# Lamp_Logic_Board_20_BRAIN_3_legs.net
KiCad netlist of a schematic drawn in EAGLE
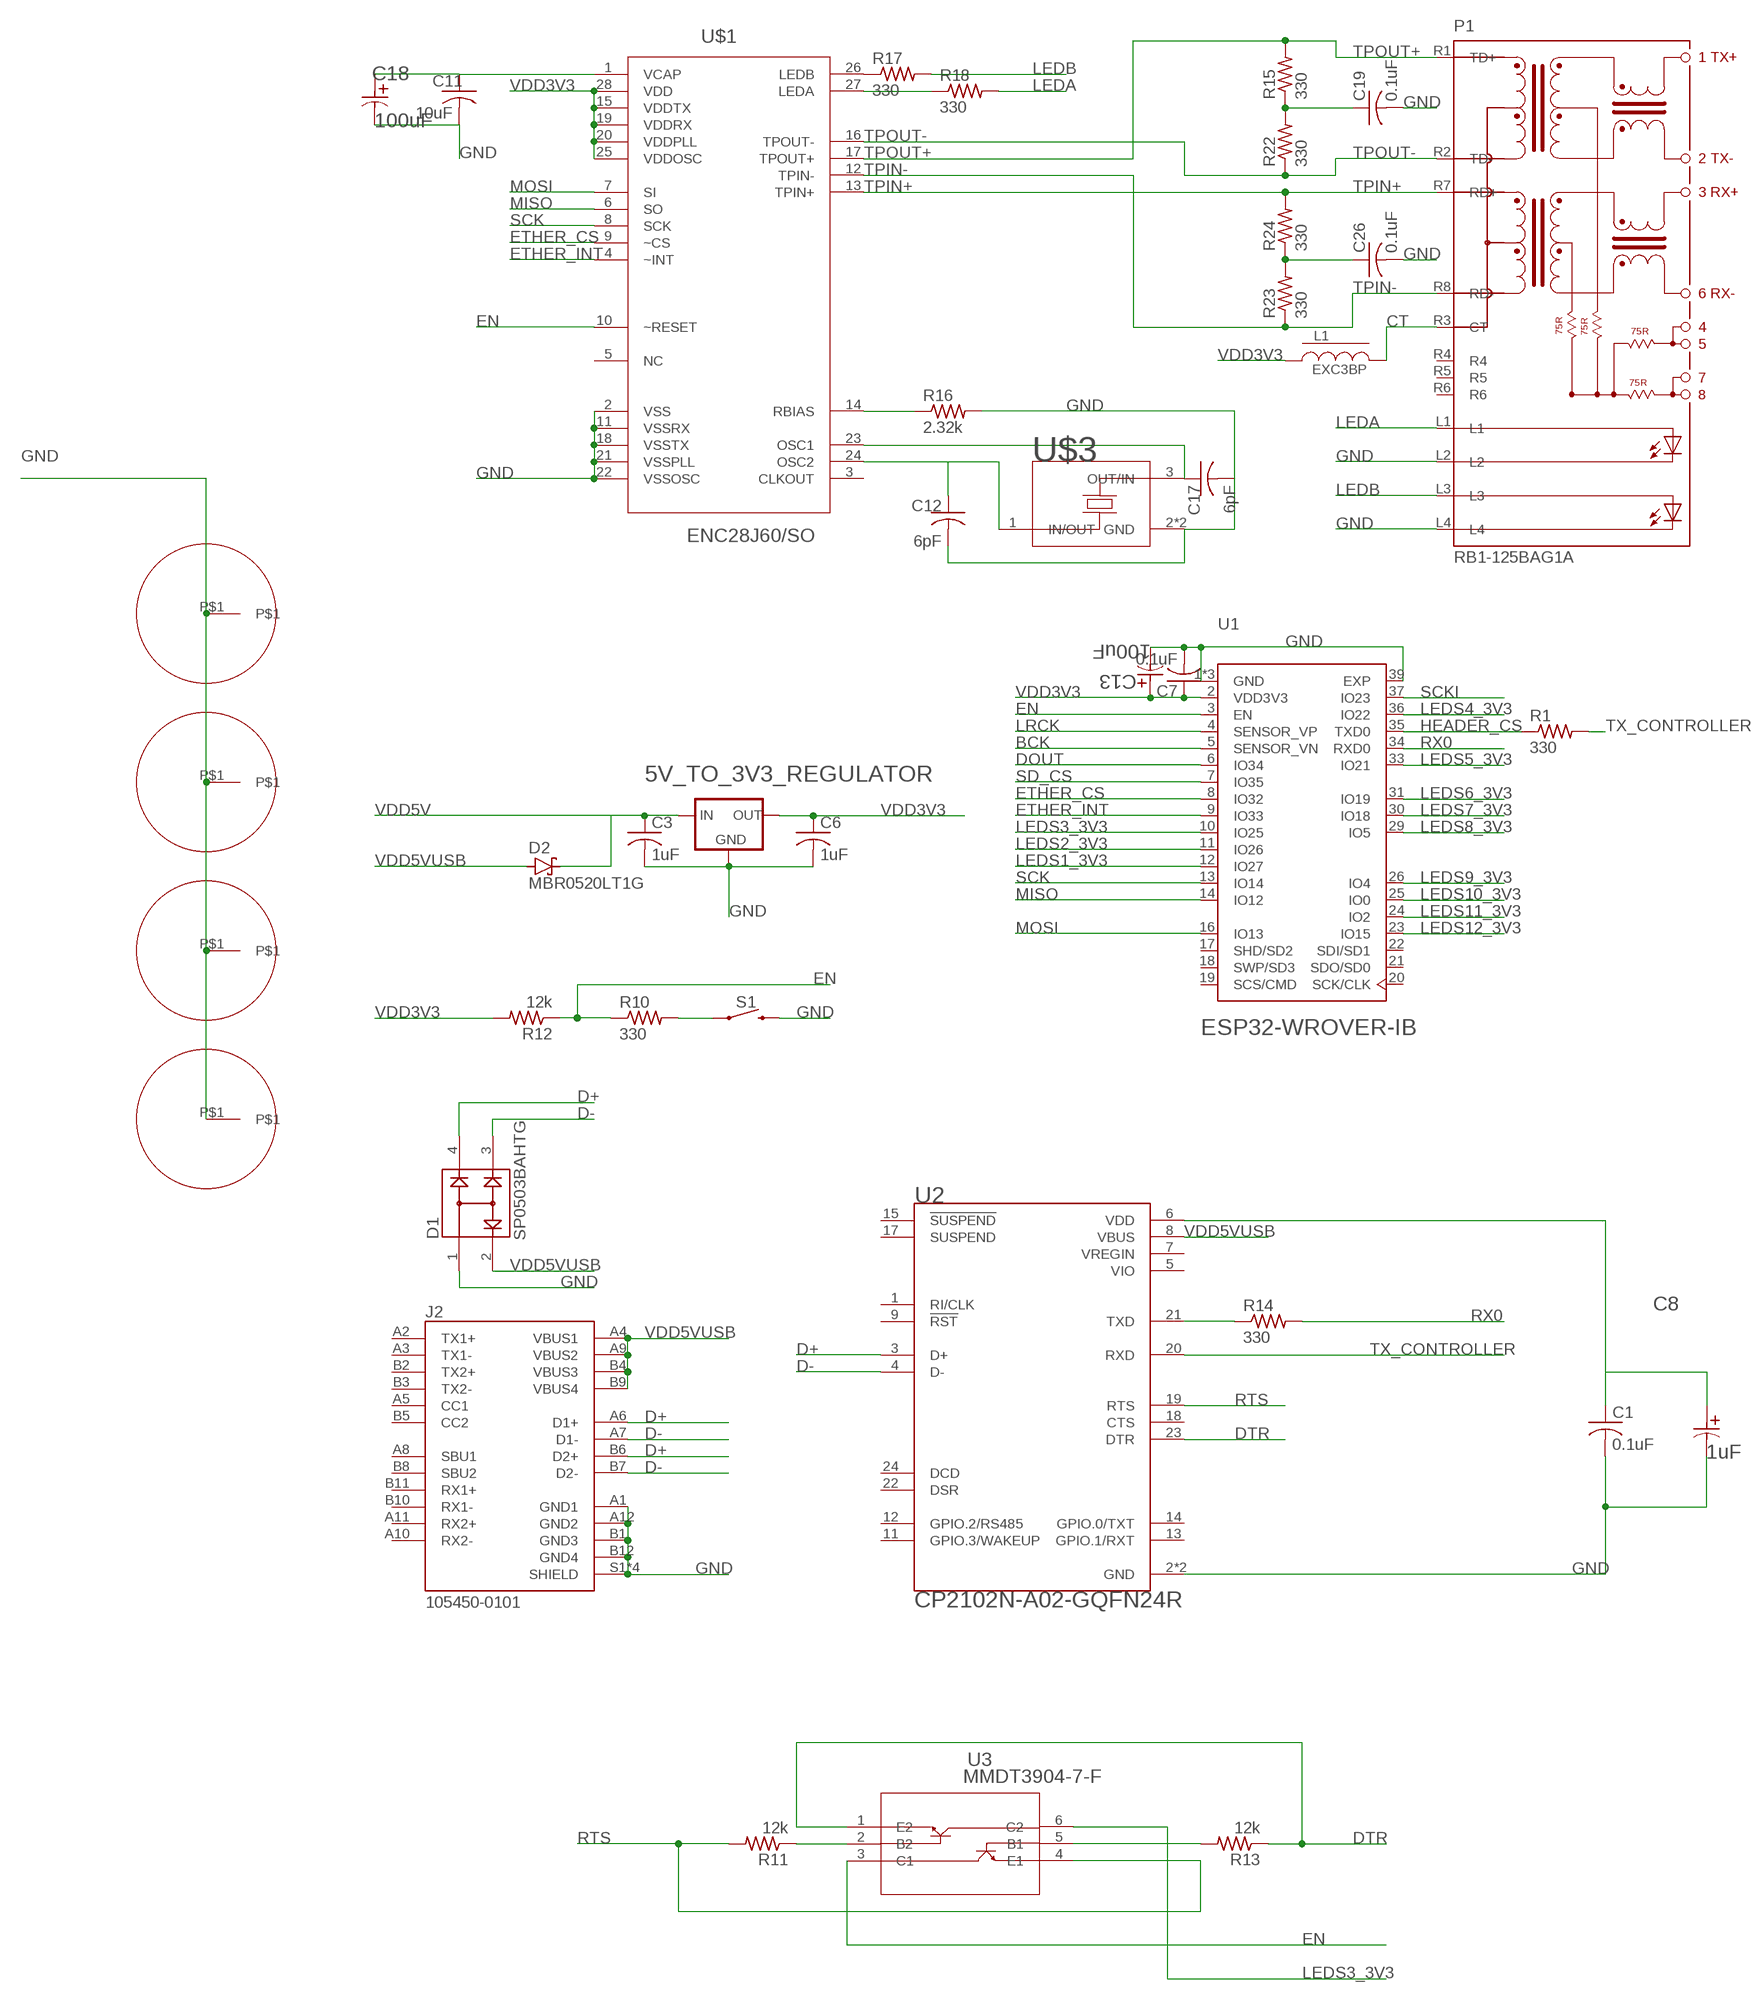
[diagram p0: schematic, sheet 1, part 1 of 2]
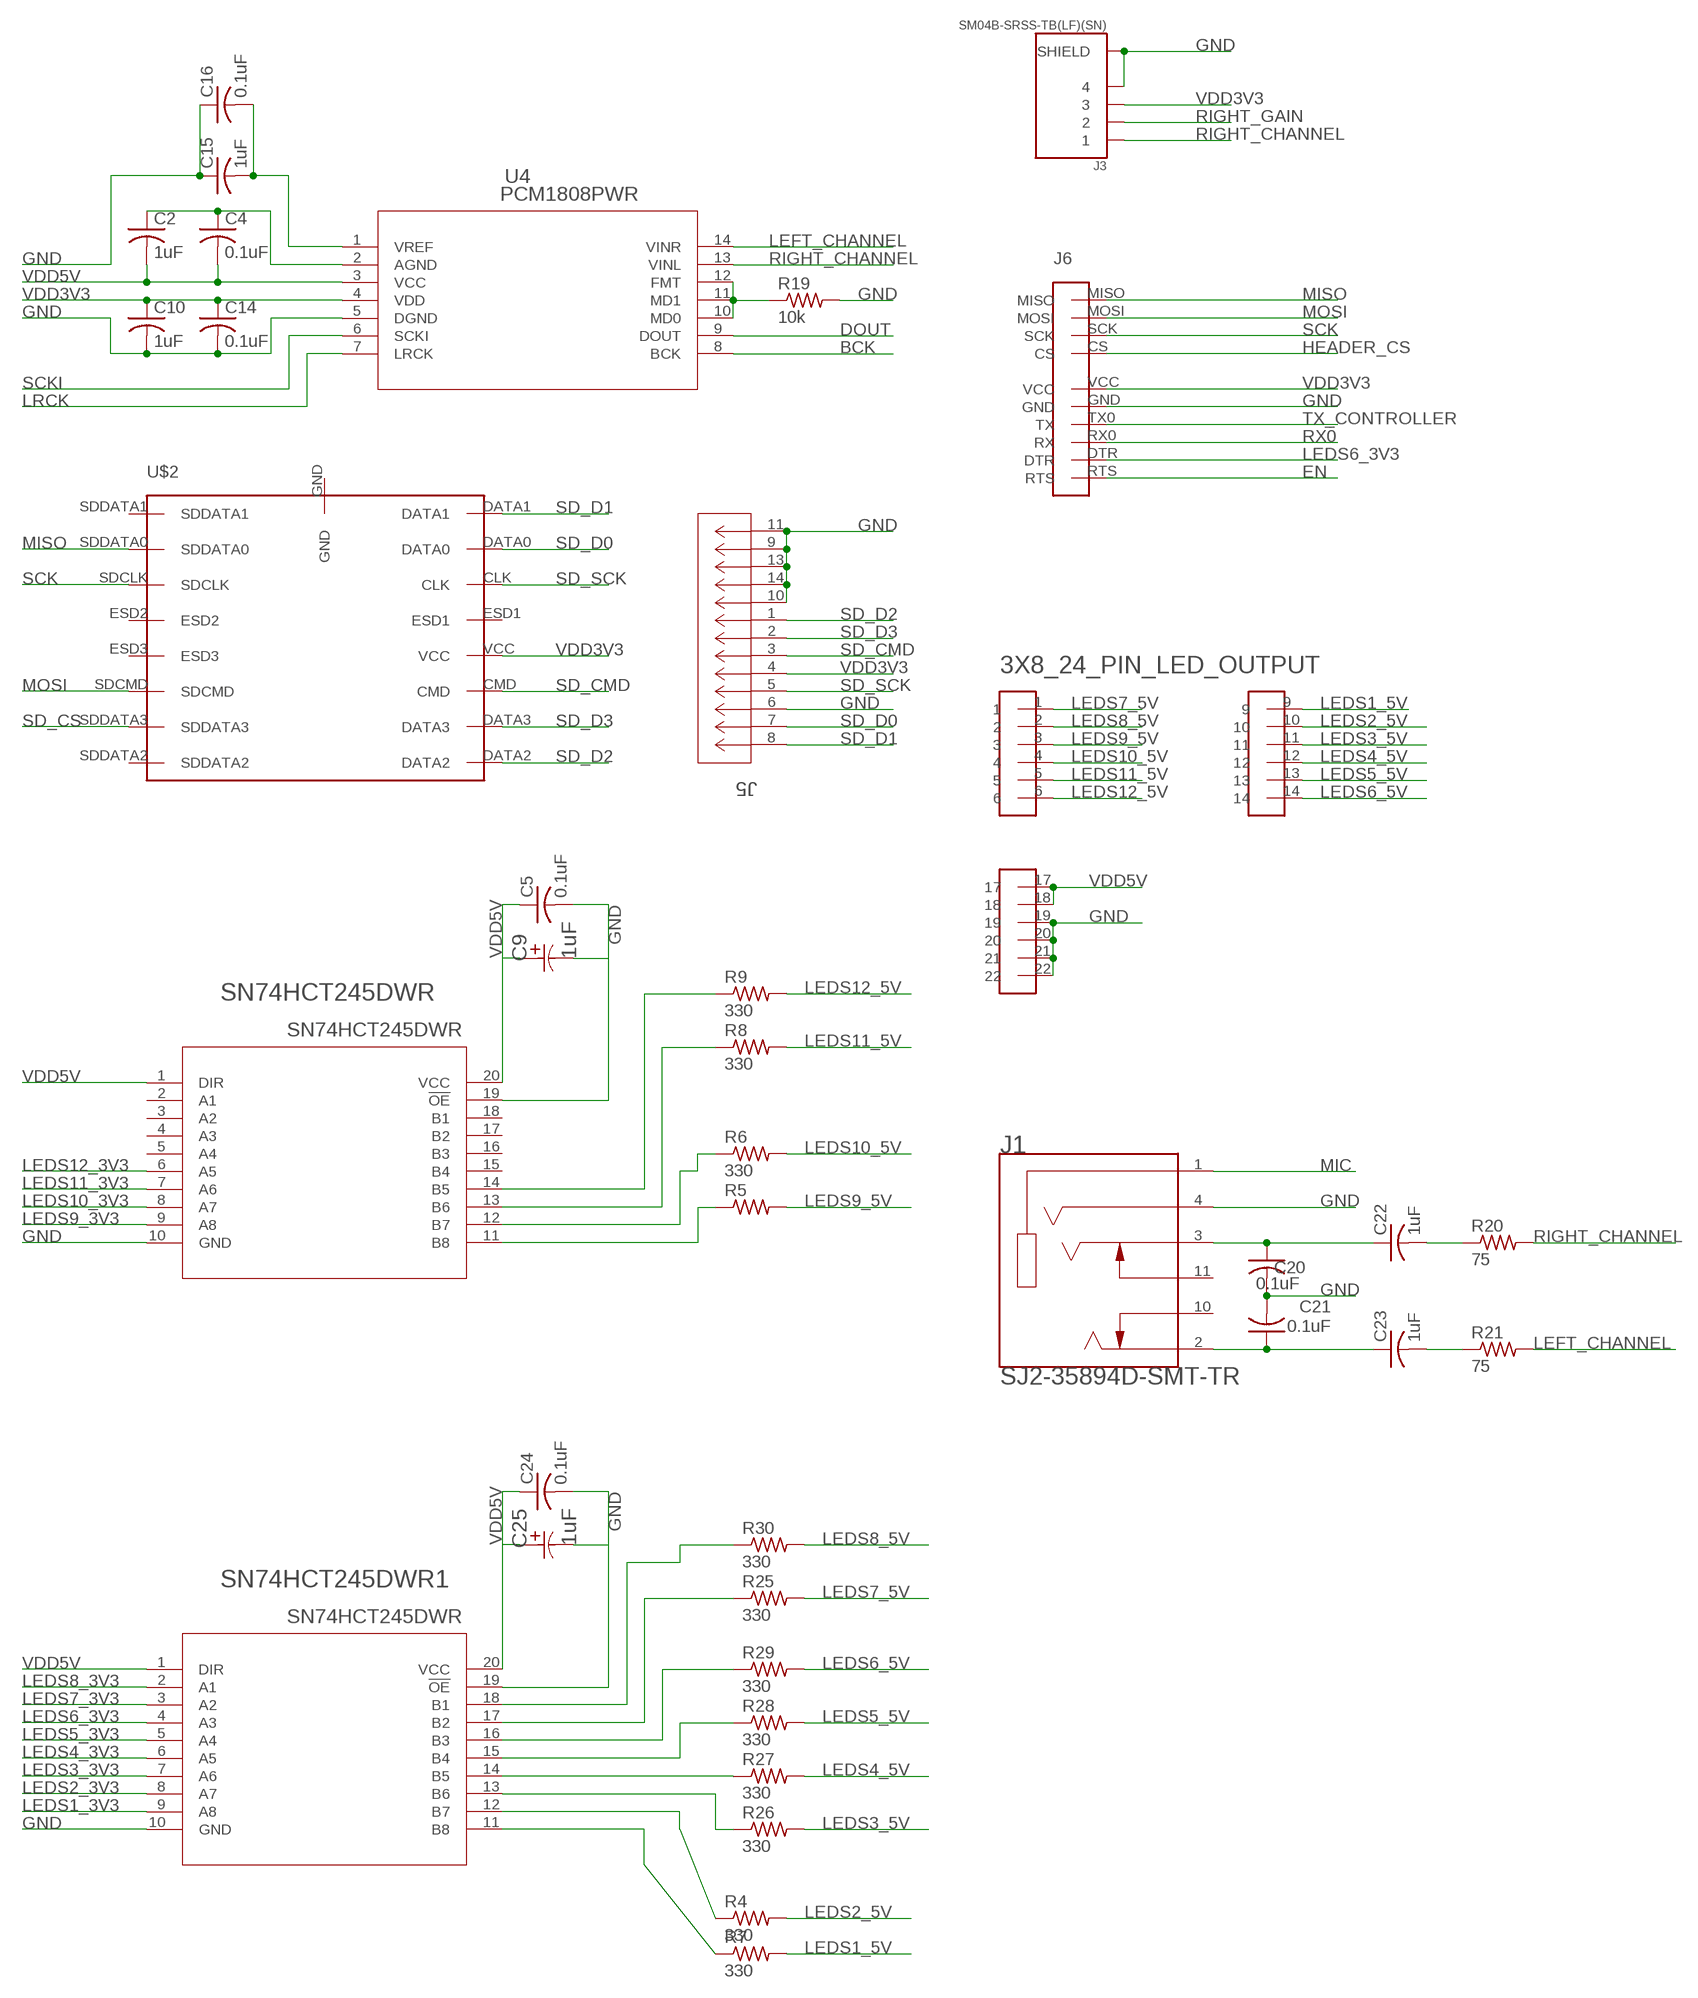
[diagram p1: schematic, sheet 1, part 2 of 2]

(export (version "E")
  (design (tool "Eeschema 10.0.6"))
  (components
    (comp (ref "3X8_24_PIN_LED_OUTPUT")
      (value "3X8PINHEAD")
      (footprint "eagle-import:3X8PINHEAD")
      (libsource (lib "eagle-import") (part "3X8PINHEAD"))
    )
    (comp (ref "5V_TO_3V3_REGULATOR")
      (value "LM1117MP-1.8")
      (footprint "eagle-import:SOT223")
      (fields (field (name "MF") "Texas Instruments"))
      (libsource (lib "eagle-import") (part "LM1117?-MP1.8"))
    )
    (comp (ref "C1")
      (value "0.1uF")
      (footprint "eagle-import:C0402")
      (libsource (lib "eagle-import") (part "C-USC0402"))
    )
    (comp (ref "C2")
      (value "1uF")
      (footprint "eagle-import:C0402")
      (libsource (lib "eagle-import") (part "C-USC0402"))
    )
    (comp (ref "C3")
      (value "1uF")
      (footprint "eagle-import:C0402")
      (libsource (lib "eagle-import") (part "C-USC0402"))
    )
    (comp (ref "C4")
      (value "0.1uF")
      (footprint "eagle-import:C0402")
      (libsource (lib "eagle-import") (part "C-USC0402"))
    )
    (comp (ref "C5")
      (value "0.1uF")
      (footprint "eagle-import:C0805")
      (libsource (lib "eagle-import") (part "C-USC0805"))
    )
    (comp (ref "C6")
      (value "1uF")
      (footprint "eagle-import:C0402")
      (libsource (lib "eagle-import") (part "C-USC0402"))
    )
    (comp (ref "C7")
      (value "0.1uF")
      (footprint "eagle-import:C0402")
      (libsource (lib "eagle-import") (part "C-USC0402"))
    )
    (comp (ref "C8")
      (value "1uF")
      (footprint "eagle-import:CAP_EEFC_B")
      (fields (field (name "MANUFACTURER_PART_NUMBER") "EEEFC1V1R0R"))
      (libsource (lib "eagle-import") (part "EEEFC1V1R0R"))
    )
    (comp (ref "C9")
      (value "1uF")
      (footprint "eagle-import:CAP_EEFC_B")
      (fields (field (name "MANUFACTURER_PART_NUMBER") "EEEFC1V1R0R"))
      (libsource (lib "eagle-import") (part "EEEFC1V1R0R"))
    )
    (comp (ref "C10")
      (value "1uF")
      (footprint "eagle-import:C0402")
      (libsource (lib "eagle-import") (part "C-USC0402"))
    )
    (comp (ref "C11")
      (value "10uF")
      (footprint "eagle-import:C0402")
      (libsource (lib "eagle-import") (part "C-USC0402"))
    )
    (comp (ref "C12")
      (value "6pF")
      (footprint "eagle-import:C0402")
      (libsource (lib "eagle-import") (part "C-USC0402"))
    )
    (comp (ref "C13")
      (value "100uF")
      (footprint "eagle-import:CAP_EEFC_B")
      (fields (field (name "MANUFACTURER_PART_NUMBER") "EEEFC1V1R0R"))
      (libsource (lib "eagle-import") (part "EEEFC1V1R0R"))
    )
    (comp (ref "C14")
      (value "0.1uF")
      (footprint "eagle-import:C0402")
      (libsource (lib "eagle-import") (part "C-USC0402"))
    )
    (comp (ref "C15")
      (value "1uF")
      (footprint "eagle-import:C0402")
      (libsource (lib "eagle-import") (part "C-USC0402"))
    )
    (comp (ref "C16")
      (value "0.1uF")
      (footprint "eagle-import:C0402")
      (libsource (lib "eagle-import") (part "C-USC0402"))
    )
    (comp (ref "C17")
      (value "6pF")
      (footprint "eagle-import:C0402")
      (libsource (lib "eagle-import") (part "C-USC0402"))
    )
    (comp (ref "C18")
      (value "100uF")
      (footprint "eagle-import:CAP_EEFC_B")
      (fields (field (name "MANUFACTURER_PART_NUMBER") "EEEFC1V1R0R"))
      (libsource (lib "eagle-import") (part "EEEFC1V1R0R"))
    )
    (comp (ref "C19")
      (value "0.1uF")
      (footprint "eagle-import:C0402")
      (libsource (lib "eagle-import") (part "C-USC0402"))
    )
    (comp (ref "C20")
      (value "0.1uF")
      (footprint "eagle-import:C0805")
      (libsource (lib "eagle-import") (part "C-USC0805"))
    )
    (comp (ref "C21")
      (value "0.1uF")
      (footprint "eagle-import:C0805")
      (libsource (lib "eagle-import") (part "C-USC0805"))
    )
    (comp (ref "C22")
      (value "1uF")
      (footprint "eagle-import:C0402")
      (libsource (lib "eagle-import") (part "C-USC0402"))
    )
    (comp (ref "C23")
      (value "1uF")
      (footprint "eagle-import:C0402")
      (libsource (lib "eagle-import") (part "C-USC0402"))
    )
    (comp (ref "C24")
      (value "0.1uF")
      (footprint "eagle-import:C0805")
      (libsource (lib "eagle-import") (part "C-USC0805"))
    )
    (comp (ref "C25")
      (value "1uF")
      (footprint "eagle-import:CAP_EEFC_B")
      (fields (field (name "MANUFACTURER_PART_NUMBER") "EEEFC1V1R0R"))
      (libsource (lib "eagle-import") (part "EEEFC1V1R0R"))
    )
    (comp (ref "C26")
      (value "0.1uF")
      (footprint "eagle-import:C0402")
      (libsource (lib "eagle-import") (part "C-USC0402"))
    )
    (comp (ref "D1")
      (value "SP0503BAHTG")
      (footprint "eagle-import:SOT143")
      (fields (field (name "DIGI-KEY_PART_NUMBER") "F2715CT-ND") (field (name "MF") "Littelfuse Inc."))
      (libsource (lib "eagle-import") (part "SP0503BAHTG"))
    )
    (comp (ref "D2")
      (value "MBR0520LT1G")
      (footprint "eagle-import:SOD-123")
      (fields
        (field (name "DIGIKEY_PART_NUMBER") "MBR0520LT1GOSTR-ND")
        (field (name "MANUFACTURER") "ON Semiconductor")
        (field (name "CREATED_BY") "PCBLayout.com")
      )
      (libsource (lib "eagle-import") (part "MBR0520LT1G"))
    )
    (comp (ref "J1")
      (value "SJ2-35894D-SMT-TR")
      (footprint "eagle-import:CUI_SJ2-35894D-SMT-TR")
      (fields (field (name "DIGI-KEY_PART_NUMBER") "CP-SJ2-35894D-SMT-CT-ND") (field (name "MF") "CUI Inc."))
      (libsource (lib "eagle-import") (part "SJ2-35894D-SMT-TR"))
    )
    (comp (ref "J2")
      (value "105450-0101")
      (footprint "eagle-import:MOLEX_105450-0101")
      (fields
        (field (name "DIGI-KEY_PART_NUMBER") "WM12856CT-ND")
        (field (name "MF") "Molex")
        (field (name "MP") "1054500101")
      )
      (libsource (lib "eagle-import") (part "105450-0101"))
    )
    (comp (ref "J3")
      (value "SM04B-SRSS-TB(LF)(SN)")
      (footprint "eagle-import:JST_SM04B-SRSS-TB(LF)(SN)")
      (fields (field (name "MF") "JST Sales") (field (name "MP") "SM04B-SRSS-TB_LF__SN_"))
      (libsource (lib "eagle-import") (part "SM04B-SRSS-TB(LF)(SN)"))
    )
    (comp (ref "J5")
      (value "LLC")
      (footprint "eagle-import:CON00218_8")
      (libsource (lib "eagle-import") (part "LLC"))
    )
    (comp (ref "J6")
      (value "2X6PINHEAD")
      (footprint "eagle-import:2X6PINHEAD")
      (libsource (lib "eagle-import") (part "2X6PINHEAD"))
    )
    (comp (ref "L1")
      (value "EXC3BP")
      (footprint "eagle-import:L0603")
      (libsource (lib "eagle-import") (part "EXC3BP"))
    )
    (comp (ref "P1")
      (value "RB1-125BAG1A")
      (footprint "eagle-import:WIZNET_RB1-125BAG1A")
      (fields (field (name "MF") "WIZnet"))
      (libsource (lib "eagle-import") (part "RB1-125BAG1A"))
    )
    (comp (ref "R1")
      (value "330")
      (footprint "eagle-import:RES_0603")
      (fields
        (field (name "DIGIKEY_PART_NUMBER") "311-0.0GRTR-ND")
        (field (name "MANUFACTURER") "Yageo")
        (field (name "MPN") "RC0603JR-070RL")
        (field (name "CREATED_BY") "PCBLayout.com")
      )
      (libsource (lib "eagle-import") (part "RC0603JR-070RL"))
    )
    (comp (ref "R4")
      (value "330")
      (footprint "eagle-import:RES_0603")
      (fields
        (field (name "DIGIKEY_PART_NUMBER") "311-0.0GRTR-ND")
        (field (name "MANUFACTURER") "Yageo")
        (field (name "MPN") "RC0603JR-070RL")
        (field (name "CREATED_BY") "PCBLayout.com")
      )
      (libsource (lib "eagle-import") (part "RC0603JR-070RL"))
    )
    (comp (ref "R5")
      (value "330")
      (footprint "eagle-import:RES_0603")
      (fields
        (field (name "DIGIKEY_PART_NUMBER") "311-0.0GRTR-ND")
        (field (name "MANUFACTURER") "Yageo")
        (field (name "MPN") "RC0603JR-070RL")
        (field (name "CREATED_BY") "PCBLayout.com")
      )
      (libsource (lib "eagle-import") (part "RC0603JR-070RL"))
    )
    (comp (ref "R6")
      (value "330")
      (footprint "eagle-import:RES_0603")
      (fields
        (field (name "DIGIKEY_PART_NUMBER") "311-0.0GRTR-ND")
        (field (name "MANUFACTURER") "Yageo")
        (field (name "MPN") "RC0603JR-070RL")
        (field (name "CREATED_BY") "PCBLayout.com")
      )
      (libsource (lib "eagle-import") (part "RC0603JR-070RL"))
    )
    (comp (ref "R7")
      (value "330")
      (footprint "eagle-import:RES_0603")
      (fields
        (field (name "DIGIKEY_PART_NUMBER") "311-0.0GRTR-ND")
        (field (name "MANUFACTURER") "Yageo")
        (field (name "MPN") "RC0603JR-070RL")
        (field (name "CREATED_BY") "PCBLayout.com")
      )
      (libsource (lib "eagle-import") (part "RC0603JR-070RL"))
    )
    (comp (ref "R8")
      (value "330")
      (footprint "eagle-import:RES_0603")
      (fields
        (field (name "DIGIKEY_PART_NUMBER") "311-0.0GRTR-ND")
        (field (name "MANUFACTURER") "Yageo")
        (field (name "MPN") "RC0603JR-070RL")
        (field (name "CREATED_BY") "PCBLayout.com")
      )
      (libsource (lib "eagle-import") (part "RC0603JR-070RL"))
    )
    (comp (ref "R9")
      (value "330")
      (footprint "eagle-import:RES_0603")
      (fields
        (field (name "DIGIKEY_PART_NUMBER") "311-0.0GRTR-ND")
        (field (name "MANUFACTURER") "Yageo")
        (field (name "MPN") "RC0603JR-070RL")
        (field (name "CREATED_BY") "PCBLayout.com")
      )
      (libsource (lib "eagle-import") (part "RC0603JR-070RL"))
    )
    (comp (ref "R10")
      (value "330")
      (footprint "eagle-import:RES_0603")
      (fields
        (field (name "DIGIKEY_PART_NUMBER") "311-0.0GRTR-ND")
        (field (name "MANUFACTURER") "Yageo")
        (field (name "MPN") "RC0603JR-070RL")
        (field (name "CREATED_BY") "PCBLayout.com")
      )
      (libsource (lib "eagle-import") (part "RC0603JR-070RL"))
    )
    (comp (ref "R11")
      (value "12k")
      (footprint "eagle-import:R1206")
      (libsource (lib "eagle-import") (part "R-US_R1206"))
    )
    (comp (ref "R12")
      (value "12k")
      (footprint "eagle-import:R1206")
      (libsource (lib "eagle-import") (part "R-US_R1206"))
    )
    (comp (ref "R13")
      (value "12k")
      (footprint "eagle-import:R1206")
      (libsource (lib "eagle-import") (part "R-US_R1206"))
    )
    (comp (ref "R14")
      (value "330")
      (footprint "eagle-import:RES_0603")
      (fields
        (field (name "DIGIKEY_PART_NUMBER") "311-0.0GRTR-ND")
        (field (name "MANUFACTURER") "Yageo")
        (field (name "MPN") "RC0603JR-070RL")
        (field (name "CREATED_BY") "PCBLayout.com")
      )
      (libsource (lib "eagle-import") (part "RC0603JR-070RL"))
    )
    (comp (ref "R15")
      (value "330")
      (footprint "eagle-import:RES_0603")
      (fields
        (field (name "DIGIKEY_PART_NUMBER") "311-0.0GRTR-ND")
        (field (name "MANUFACTURER") "Yageo")
        (field (name "MPN") "RC0603JR-070RL")
        (field (name "CREATED_BY") "PCBLayout.com")
      )
      (libsource (lib "eagle-import") (part "RC0603JR-070RL"))
    )
    (comp (ref "R16")
      (value "2.32k")
      (footprint "eagle-import:R1206")
      (libsource (lib "eagle-import") (part "R-US_R1206"))
    )
    (comp (ref "R17")
      (value "330")
      (footprint "eagle-import:RES_0603")
      (fields
        (field (name "DIGIKEY_PART_NUMBER") "311-0.0GRTR-ND")
        (field (name "MANUFACTURER") "Yageo")
        (field (name "MPN") "RC0603JR-070RL")
        (field (name "CREATED_BY") "PCBLayout.com")
      )
      (libsource (lib "eagle-import") (part "RC0603JR-070RL"))
    )
    (comp (ref "R18")
      (value "330")
      (footprint "eagle-import:RES_0603")
      (fields
        (field (name "DIGIKEY_PART_NUMBER") "311-0.0GRTR-ND")
        (field (name "MANUFACTURER") "Yageo")
        (field (name "MPN") "RC0603JR-070RL")
        (field (name "CREATED_BY") "PCBLayout.com")
      )
      (libsource (lib "eagle-import") (part "RC0603JR-070RL"))
    )
    (comp (ref "R19")
      (value "10k")
      (footprint "eagle-import:R1206")
      (libsource (lib "eagle-import") (part "R-US_R1206"))
    )
    (comp (ref "R20")
      (value "75")
      (footprint "eagle-import:R1206")
      (libsource (lib "eagle-import") (part "R-US_R1206"))
    )
    (comp (ref "R21")
      (value "75")
      (footprint "eagle-import:R1206")
      (libsource (lib "eagle-import") (part "R-US_R1206"))
    )
    (comp (ref "R22")
      (value "330")
      (footprint "eagle-import:RES_0603")
      (fields
        (field (name "DIGIKEY_PART_NUMBER") "311-0.0GRTR-ND")
        (field (name "MANUFACTURER") "Yageo")
        (field (name "MPN") "RC0603JR-070RL")
        (field (name "CREATED_BY") "PCBLayout.com")
      )
      (libsource (lib "eagle-import") (part "RC0603JR-070RL"))
    )
    (comp (ref "R23")
      (value "330")
      (footprint "eagle-import:RES_0603")
      (fields
        (field (name "DIGIKEY_PART_NUMBER") "311-0.0GRTR-ND")
        (field (name "MANUFACTURER") "Yageo")
        (field (name "MPN") "RC0603JR-070RL")
        (field (name "CREATED_BY") "PCBLayout.com")
      )
      (libsource (lib "eagle-import") (part "RC0603JR-070RL"))
    )
    (comp (ref "R24")
      (value "330")
      (footprint "eagle-import:RES_0603")
      (fields
        (field (name "DIGIKEY_PART_NUMBER") "311-0.0GRTR-ND")
        (field (name "MANUFACTURER") "Yageo")
        (field (name "MPN") "RC0603JR-070RL")
        (field (name "CREATED_BY") "PCBLayout.com")
      )
      (libsource (lib "eagle-import") (part "RC0603JR-070RL"))
    )
    (comp (ref "R25")
      (value "330")
      (footprint "eagle-import:RES_0603")
      (fields
        (field (name "DIGIKEY_PART_NUMBER") "311-0.0GRTR-ND")
        (field (name "MANUFACTURER") "Yageo")
        (field (name "MPN") "RC0603JR-070RL")
        (field (name "CREATED_BY") "PCBLayout.com")
      )
      (libsource (lib "eagle-import") (part "RC0603JR-070RL"))
    )
    (comp (ref "R26")
      (value "330")
      (footprint "eagle-import:RES_0603")
      (fields
        (field (name "DIGIKEY_PART_NUMBER") "311-0.0GRTR-ND")
        (field (name "MANUFACTURER") "Yageo")
        (field (name "MPN") "RC0603JR-070RL")
        (field (name "CREATED_BY") "PCBLayout.com")
      )
      (libsource (lib "eagle-import") (part "RC0603JR-070RL"))
    )
    (comp (ref "R27")
      (value "330")
      (footprint "eagle-import:RES_0603")
      (fields
        (field (name "DIGIKEY_PART_NUMBER") "311-0.0GRTR-ND")
        (field (name "MANUFACTURER") "Yageo")
        (field (name "MPN") "RC0603JR-070RL")
        (field (name "CREATED_BY") "PCBLayout.com")
      )
      (libsource (lib "eagle-import") (part "RC0603JR-070RL"))
    )
    (comp (ref "R28")
      (value "330")
      (footprint "eagle-import:RES_0603")
      (fields
        (field (name "DIGIKEY_PART_NUMBER") "311-0.0GRTR-ND")
        (field (name "MANUFACTURER") "Yageo")
        (field (name "MPN") "RC0603JR-070RL")
        (field (name "CREATED_BY") "PCBLayout.com")
      )
      (libsource (lib "eagle-import") (part "RC0603JR-070RL"))
    )
    (comp (ref "R29")
      (value "330")
      (footprint "eagle-import:RES_0603")
      (fields
        (field (name "DIGIKEY_PART_NUMBER") "311-0.0GRTR-ND")
        (field (name "MANUFACTURER") "Yageo")
        (field (name "MPN") "RC0603JR-070RL")
        (field (name "CREATED_BY") "PCBLayout.com")
      )
      (libsource (lib "eagle-import") (part "RC0603JR-070RL"))
    )
    (comp (ref "R30")
      (value "330")
      (footprint "eagle-import:RES_0603")
      (fields
        (field (name "DIGIKEY_PART_NUMBER") "311-0.0GRTR-ND")
        (field (name "MANUFACTURER") "Yageo")
        (field (name "MPN") "RC0603JR-070RL")
        (field (name "CREATED_BY") "PCBLayout.com")
      )
      (libsource (lib "eagle-import") (part "RC0603JR-070RL"))
    )
    (comp (ref "S1")
      (value "MOMENTARY-SWITCH-SPST-SMD-6.0X3.5MM")
      (footprint "eagle-import:TACTILE_SWITCH_SMD_6.0X3.5MM")
      (libsource (lib "eagle-import") (part "MOMENTARY-SWITCH-SPST-SMD-6.0X3.5MM"))
    )
    (comp (ref "SN74HCT245DWR")
      (value "SN74HCT245DWR")
      (footprint "eagle-import:DW20")
      (libsource (lib "eagle-import") (part "SN74HCT245DWR"))
    )
    (comp (ref "SN74HCT245DWR1")
      (value "SN74HCT245DWR")
      (footprint "eagle-import:DW20")
      (libsource (lib "eagle-import") (part "SN74HCT245DWR"))
    )
    (comp (ref "U$1")
      (value "ENC28J60/SO")
      (footprint "eagle-import:SOIC127P1034X264-28N")
      (fields
        (field (name "DIGI-KEY_PART_NUMBER") "ENC28J60/SS-ND")
        (field (name "MF") "Microchip")
        (field (name "MP") "ENC28J60/SS")
      )
      (libsource (lib "eagle-import") (part "ENC28J60/SO"))
    )
    (comp (ref "U$2")
      (value "CM1624-08DE")
      (footprint "eagle-import:CM1624-08DE")
      (libsource (lib "eagle-import") (part "CM1624-08DE"))
    )
    (comp (ref "U$3")
      (value "ECS-250-10-37B-CTN-TR")
      (footprint "eagle-import:ECS-250-10-37B-CTN-TR")
      (libsource (lib "eagle-import") (part "ECS-250-10-37B-CTN-TR"))
    )
    (comp (ref "U$4")
      (value "QUICKFIT_RISER_THING")
      (footprint "eagle-import:QUICKFIT_RISER_THING")
      (libsource (lib "eagle-import") (part "QUICKFIT_RISER_THING"))
    )
    (comp (ref "U$5")
      (value "QUICKFIT_RISER_THING")
      (footprint "eagle-import:QUICKFIT_RISER_THING")
      (libsource (lib "eagle-import") (part "QUICKFIT_RISER_THING"))
    )
    (comp (ref "U$6")
      (value "QUICKFIT_RISER_THING")
      (footprint "eagle-import:QUICKFIT_RISER_THING")
      (libsource (lib "eagle-import") (part "QUICKFIT_RISER_THING"))
    )
    (comp (ref "U$8")
      (value "QUICKFIT_RISER_THING")
      (footprint "eagle-import:QUICKFIT_RISER_THING")
      (libsource (lib "eagle-import") (part "QUICKFIT_RISER_THING"))
    )
    (comp (ref "U1")
      (value "ESP32-WROVER-IB")
      (footprint "eagle-import:XCVR_ESP32-WROVER-I")
      (fields (field (name "MF") "Espressif Systems") (field (name "MP") "ESP32-WROVER-I"))
      (libsource (lib "eagle-import") (part "ESP32-WROVER-I"))
    )
    (comp (ref "U2")
      (value "CP2102N-A02-GQFN24R")
      (footprint "eagle-import:SILABS_CP2102N-A02-GQFN24R")
      (libsource (lib "eagle-import") (part "CP2102N-A02-GQFN24R"))
    )
    (comp (ref "U3")
      (value "MMDT3904-7-F")
      (footprint "eagle-import:SOT-363")
      (fields (field (name "MANUFACTURER_PART_NUMBER") "MMDT39047F"))
      (libsource (lib "eagle-import") (part "MMDT3904-7-F"))
    )
    (comp (ref "U4")
      (value "PCM1808PWR")
      (footprint "eagle-import:PW14")
      (libsource (lib "eagle-import") (part "PCM1808PWR"))
    )
  )
  (nets
    (net (code "1") (name "BCK") (class "Default")
      (node (ref "U1") (pin "5") (pinfunction "SENSOR_VN_5") (pintype "input"))
      (node (ref "U4") (pin "8") (pinfunction "BCK_8") (pintype "bidirectional"))
    )
    (net (code "2") (name "CT") (class "Default")
      (node (ref "L1") (pin "2") (pinfunction "2_2") (pintype "passive"))
      (node (ref "P1") (pin "R3") (pinfunction "CT_R3") (pintype "input"))
    )
    (net (code "3") (name "D+") (class "Default")
      (node (ref "D1") (pin "4") (pinfunction "4_4") (pintype "passive"))
      (node (ref "J2") (pin "A6") (pinfunction "D1+_A6") (pintype "passive"))
      (node (ref "J2") (pin "B6") (pinfunction "D2+_B6") (pintype "passive"))
      (node (ref "U2") (pin "3") (pinfunction "D+_3") (pintype "bidirectional"))
    )
    (net (code "4") (name "D-") (class "Default")
      (node (ref "D1") (pin "3") (pinfunction "3_3") (pintype "passive"))
      (node (ref "J2") (pin "A7") (pinfunction "D1-_A7") (pintype "passive"))
      (node (ref "J2") (pin "B7") (pinfunction "D2-_B7") (pintype "passive"))
      (node (ref "U2") (pin "4") (pinfunction "D-_4") (pintype "bidirectional"))
    )
    (net (code "5") (name "DOUT") (class "Default")
      (node (ref "U1") (pin "6") (pinfunction "IO34_6") (pintype "input"))
      (node (ref "U4") (pin "9") (pinfunction "DOUT_9") (pintype "output"))
    )
    (net (code "6") (name "DTR") (class "Default")
      (node (ref "R13") (pin "1") (pinfunction "1_1") (pintype "passive"))
      (node (ref "U2") (pin "23") (pinfunction "DTR_23") (pintype "bidirectional"))
      (node (ref "U3") (pin "1") (pinfunction "E2_1") (pintype "passive"))
    )
    (net (code "7") (name "EN") (class "Default")
      (node (ref "J6") (pin "RTS") (pinfunction "RTS_RTS") (pintype "bidirectional"))
      (node (ref "R10") (pin "1") (pinfunction "1_1") (pintype "passive"))
      (node (ref "R12") (pin "1") (pinfunction "1_1") (pintype "passive"))
      (node (ref "U$1") (pin "10") (pinfunction "~{RESET}_10") (pintype "input"))
      (node (ref "U1") (pin "3") (pinfunction "EN_3") (pintype "input"))
      (node (ref "U3") (pin "3") (pinfunction "C1_3") (pintype "passive"))
    )
    (net (code "8") (name "ETHER_CS") (class "Default")
      (node (ref "U$1") (pin "9") (pinfunction "~{CS}_9") (pintype "input"))
      (node (ref "U1") (pin "8") (pinfunction "IO32_8") (pintype "bidirectional"))
    )
    (net (code "9") (name "ETHER_INT") (class "Default")
      (node (ref "U$1") (pin "4") (pinfunction "~{INT}_4") (pintype "output"))
      (node (ref "U1") (pin "9") (pinfunction "IO33_9") (pintype "bidirectional"))
    )
    (net (code "10") (name "GND") (class "Default")
      (node (ref "3X8_24_PIN_LED_OUTPUT") (pin "19") (pinfunction "19_19") (pintype "bidirectional"))
      (node (ref "3X8_24_PIN_LED_OUTPUT") (pin "20") (pinfunction "20_20") (pintype "bidirectional"))
      (node (ref "3X8_24_PIN_LED_OUTPUT") (pin "21") (pinfunction "21_21") (pintype "bidirectional"))
      (node (ref "3X8_24_PIN_LED_OUTPUT") (pin "22") (pinfunction "22_22") (pintype "bidirectional"))
      (node (ref "5V_TO_3V3_REGULATOR") (pin "1") (pinfunction "GND_1") (pintype "input"))
      (node (ref "C1") (pin "2") (pinfunction "2_2") (pintype "passive"))
      (node (ref "C10") (pin "2") (pinfunction "2_2") (pintype "passive"))
      (node (ref "C11") (pin "2") (pinfunction "2_2") (pintype "passive"))
      (node (ref "C12") (pin "2") (pinfunction "2_2") (pintype "passive"))
      (node (ref "C13") (pin "2") (pinfunction "2_2") (pintype "passive"))
      (node (ref "C14") (pin "2") (pinfunction "2_2") (pintype "passive"))
      (node (ref "C15") (pin "1") (pinfunction "1_1") (pintype "passive"))
      (node (ref "C16") (pin "1") (pinfunction "1_1") (pintype "passive"))
      (node (ref "C17") (pin "2") (pinfunction "2_2") (pintype "passive"))
      (node (ref "C18") (pin "2") (pinfunction "2_2") (pintype "passive"))
      (node (ref "C19") (pin "2") (pinfunction "2_2") (pintype "passive"))
      (node (ref "C20") (pin "2") (pinfunction "2_2") (pintype "passive"))
      (node (ref "C21") (pin "2") (pinfunction "2_2") (pintype "passive"))
      (node (ref "C24") (pin "2") (pinfunction "2_2") (pintype "passive"))
      (node (ref "C25") (pin "2") (pinfunction "2_2") (pintype "passive"))
      (node (ref "C26") (pin "2") (pinfunction "2_2") (pintype "passive"))
      (node (ref "C3") (pin "2") (pinfunction "2_2") (pintype "passive"))
      (node (ref "C5") (pin "2") (pinfunction "2_2") (pintype "passive"))
      (node (ref "C6") (pin "2") (pinfunction "2_2") (pintype "passive"))
      (node (ref "C7") (pin "2") (pinfunction "2_2") (pintype "passive"))
      (node (ref "C8") (pin "2") (pinfunction "2_2") (pintype "passive"))
      (node (ref "C9") (pin "2") (pinfunction "2_2") (pintype "passive"))
      (node (ref "D1") (pin "1") (pinfunction "1_1") (pintype "passive"))
      (node (ref "J1") (pin "4") (pinfunction "RING2_4") (pintype "passive"))
      (node (ref "J2") (pin "A1") (pinfunction "GND1_A1") (pintype "passive"))
      (node (ref "J2") (pin "A12") (pinfunction "GND2_A12") (pintype "passive"))
      (node (ref "J2") (pin "B1") (pinfunction "GND3_B1") (pintype "passive"))
      (node (ref "J2") (pin "B12") (pinfunction "GND4_B12") (pintype "passive"))
      (node (ref "J2") (pin "S1") (pinfunction "SHIELD_S1") (pintype "passive"))
      (node (ref "J2") (pin "S2") (pinfunction "SHIELD_S2") (pintype "passive"))
      (node (ref "J2") (pin "S3") (pinfunction "SHIELD_S3") (pintype "passive"))
      (node (ref "J2") (pin "S4") (pinfunction "SHIELD_S4") (pintype "passive"))
      (node (ref "J3") (pin "4") (pinfunction "4_4") (pintype "passive"))
      (node (ref "J3") (pin "S1") (pinfunction "SHIELD_S1") (pintype "passive"))
      (node (ref "J3") (pin "S2") (pinfunction "SHIELD_S2") (pintype "passive"))
      (node (ref "J5") (pin "10") (pinfunction "10_10") (pintype "passive"))
      (node (ref "J5") (pin "11") (pinfunction "11_11") (pintype "passive"))
      (node (ref "J5") (pin "13") (pinfunction "13_13") (pintype "passive"))
      (node (ref "J5") (pin "14") (pinfunction "14_14") (pintype "passive"))
      (node (ref "J5") (pin "6") (pinfunction "6_6") (pintype "passive"))
      (node (ref "J5") (pin "9") (pinfunction "9_9") (pintype "passive"))
      (node (ref "J6") (pin "GND") (pinfunction "GND_GND") (pintype "bidirectional"))
      (node (ref "P1") (pin "L2") (pinfunction "L2_L2") (pintype "passive"))
      (node (ref "P1") (pin "L4") (pinfunction "L4_L4") (pintype "passive"))
      (node (ref "R16") (pin "2") (pinfunction "2_2") (pintype "passive"))
      (node (ref "R19") (pin "2") (pinfunction "2_2") (pintype "passive"))
      (node (ref "S1") (pin "2") (pinfunction "2_2") (pintype "passive"))
      (node (ref "SN74HCT245DWR") (pin "10") (pinfunction "GND_10") (pintype "power_in"))
      (node (ref "SN74HCT245DWR") (pin "19") (pinfunction "~{OE}_19") (pintype "input"))
      (node (ref "SN74HCT245DWR1") (pin "10") (pinfunction "GND_10") (pintype "power_in"))
      (node (ref "SN74HCT245DWR1") (pin "19") (pinfunction "~{OE}_19") (pintype "input"))
      (node (ref "U$1") (pin "11") (pinfunction "VSSRX_11") (pintype "power_in"))
      (node (ref "U$1") (pin "18") (pinfunction "VSSTX_18") (pintype "power_in"))
      (node (ref "U$1") (pin "2") (pinfunction "VSS_2") (pintype "power_in"))
      (node (ref "U$1") (pin "21") (pinfunction "VSSPLL_21") (pintype "power_in"))
      (node (ref "U$1") (pin "22") (pinfunction "VSSOSC_22") (pintype "power_in"))
      (node (ref "U$3") (pin "2") (pinfunction "GND_2") (pintype "bidirectional"))
      (node (ref "U$3") (pin "4") (pinfunction "GND_4") (pintype "bidirectional"))
      (node (ref "U$4") (pin "P$1") (pinfunction "P$1_P$1") (pintype "bidirectional"))
      (node (ref "U$5") (pin "P$1") (pinfunction "P$1_P$1") (pintype "bidirectional"))
      (node (ref "U$6") (pin "P$1") (pinfunction "P$1_P$1") (pintype "bidirectional"))
      (node (ref "U$8") (pin "P$1") (pinfunction "P$1_P$1") (pintype "bidirectional"))
      (node (ref "U1") (pin "1") (pinfunction "GND_1") (pintype "power_in"))
      (node (ref "U1") (pin "15") (pinfunction "GND_15") (pintype "power_in"))
      (node (ref "U1") (pin "38") (pinfunction "GND_38") (pintype "power_in"))
      (node (ref "U1") (pin "39") (pinfunction "EXP_39") (pintype "power_in"))
      (node (ref "U2") (pin "2") (pinfunction "GND_2") (pintype "power_in"))
      (node (ref "U2") (pin "25") (pinfunction "GND_25") (pintype "power_in"))
      (node (ref "U4") (pin "5") (pinfunction "DGND_5") (pintype "power_in"))
    )
    (net (code "11") (name "HEADER_CS") (class "Default")
      (node (ref "J6") (pin "CS") (pinfunction "CS_CS") (pintype "bidirectional"))
      (node (ref "R1") (pin "1") (pinfunction "1_1") (pintype "passive"))
      (node (ref "U1") (pin "35") (pinfunction "TXD0_35") (pintype "bidirectional"))
    )
    (net (code "12") (name "LEDA") (class "Default")
      (node (ref "P1") (pin "L1") (pinfunction "L1_L1") (pintype "passive"))
      (node (ref "R18") (pin "2") (pinfunction "2_2") (pintype "passive"))
    )
    (net (code "13") (name "LEDB") (class "Default")
      (node (ref "P1") (pin "L3") (pinfunction "L3_L3") (pintype "passive"))
      (node (ref "R17") (pin "2") (pinfunction "2_2") (pintype "passive"))
    )
    (net (code "14") (name "LEDS1_3V3") (class "Default")
      (node (ref "SN74HCT245DWR1") (pin "9") (pinfunction "A8_9") (pintype "bidirectional"))
      (node (ref "U1") (pin "12") (pinfunction "IO27_12") (pintype "bidirectional"))
    )
    (net (code "15") (name "LEDS1_5V") (class "Default")
      (node (ref "3X8_24_PIN_LED_OUTPUT") (pin "9") (pinfunction "9_9") (pintype "bidirectional"))
      (node (ref "R7") (pin "2") (pinfunction "2_2") (pintype "passive"))
    )
    (net (code "16") (name "LEDS2_3V3") (class "Default")
      (node (ref "SN74HCT245DWR1") (pin "8") (pinfunction "A7_8") (pintype "bidirectional"))
      (node (ref "U1") (pin "11") (pinfunction "IO26_11") (pintype "bidirectional"))
    )
    (net (code "17") (name "LEDS2_5V") (class "Default")
      (node (ref "3X8_24_PIN_LED_OUTPUT") (pin "10") (pinfunction "10_10") (pintype "bidirectional"))
      (node (ref "R4") (pin "2") (pinfunction "2_2") (pintype "passive"))
    )
    (net (code "18") (name "LEDS3_3V3") (class "Default")
      (node (ref "SN74HCT245DWR1") (pin "7") (pinfunction "A6_7") (pintype "bidirectional"))
      (node (ref "U1") (pin "10") (pinfunction "IO25_10") (pintype "bidirectional"))
      (node (ref "U3") (pin "6") (pinfunction "C2_6") (pintype "passive"))
    )
    (net (code "19") (name "LEDS3_5V") (class "Default")
      (node (ref "3X8_24_PIN_LED_OUTPUT") (pin "11") (pinfunction "11_11") (pintype "bidirectional"))
      (node (ref "R26") (pin "2") (pinfunction "2_2") (pintype "passive"))
    )
    (net (code "20") (name "LEDS4_3V3") (class "Default")
      (node (ref "SN74HCT245DWR1") (pin "6") (pinfunction "A5_6") (pintype "bidirectional"))
      (node (ref "U1") (pin "36") (pinfunction "IO22_36") (pintype "bidirectional"))
    )
    (net (code "21") (name "LEDS4_5V") (class "Default")
      (node (ref "3X8_24_PIN_LED_OUTPUT") (pin "12") (pinfunction "12_12") (pintype "bidirectional"))
      (node (ref "R27") (pin "2") (pinfunction "2_2") (pintype "passive"))
    )
    (net (code "22") (name "LEDS5_3V3") (class "Default")
      (node (ref "SN74HCT245DWR1") (pin "5") (pinfunction "A4_5") (pintype "bidirectional"))
      (node (ref "U1") (pin "33") (pinfunction "IO21_33") (pintype "bidirectional"))
    )
    (net (code "23") (name "LEDS5_5V") (class "Default")
      (node (ref "3X8_24_PIN_LED_OUTPUT") (pin "13") (pinfunction "13_13") (pintype "bidirectional"))
      (node (ref "R28") (pin "2") (pinfunction "2_2") (pintype "passive"))
    )
    (net (code "24") (name "LEDS6_3V3") (class "Default")
      (node (ref "J6") (pin "DTR") (pinfunction "DTR_DTR") (pintype "bidirectional"))
      (node (ref "SN74HCT245DWR1") (pin "4") (pinfunction "A3_4") (pintype "bidirectional"))
      (node (ref "U1") (pin "31") (pinfunction "IO19_31") (pintype "bidirectional"))
    )
    (net (code "25") (name "LEDS6_5V") (class "Default")
      (node (ref "3X8_24_PIN_LED_OUTPUT") (pin "14") (pinfunction "14_14") (pintype "bidirectional"))
      (node (ref "R29") (pin "2") (pinfunction "2_2") (pintype "passive"))
    )
    (net (code "26") (name "LEDS7_3V3") (class "Default")
      (node (ref "SN74HCT245DWR1") (pin "3") (pinfunction "A2_3") (pintype "bidirectional"))
      (node (ref "U1") (pin "30") (pinfunction "IO18_30") (pintype "bidirectional"))
    )
    (net (code "27") (name "LEDS7_5V") (class "Default")
      (node (ref "3X8_24_PIN_LED_OUTPUT") (pin "1") (pinfunction "1_1") (pintype "bidirectional"))
      (node (ref "R25") (pin "2") (pinfunction "2_2") (pintype "passive"))
    )
    (net (code "28") (name "LEDS8_3V3") (class "Default")
      (node (ref "SN74HCT245DWR1") (pin "2") (pinfunction "A1_2") (pintype "bidirectional"))
      (node (ref "U1") (pin "29") (pinfunction "IO5_29") (pintype "bidirectional"))
    )
    (net (code "29") (name "LEDS8_5V") (class "Default")
      (node (ref "3X8_24_PIN_LED_OUTPUT") (pin "2") (pinfunction "2_2") (pintype "bidirectional"))
      (node (ref "R30") (pin "2") (pinfunction "2_2") (pintype "passive"))
    )
    (net (code "30") (name "LEDS9_3V3") (class "Default")
      (node (ref "SN74HCT245DWR") (pin "9") (pinfunction "A8_9") (pintype "bidirectional"))
      (node (ref "U1") (pin "26") (pinfunction "IO4_26") (pintype "bidirectional"))
    )
    (net (code "31") (name "LEDS9_5V") (class "Default")
      (node (ref "3X8_24_PIN_LED_OUTPUT") (pin "3") (pinfunction "3_3") (pintype "bidirectional"))
      (node (ref "R5") (pin "2") (pinfunction "2_2") (pintype "passive"))
    )
    (net (code "32") (name "LEDS10_3V3") (class "Default")
      (node (ref "SN74HCT245DWR") (pin "8") (pinfunction "A7_8") (pintype "bidirectional"))
      (node (ref "U1") (pin "25") (pinfunction "IO0_25") (pintype "bidirectional"))
    )
    (net (code "33") (name "LEDS10_5V") (class "Default")
      (node (ref "3X8_24_PIN_LED_OUTPUT") (pin "4") (pinfunction "4_4") (pintype "bidirectional"))
      (node (ref "R6") (pin "2") (pinfunction "2_2") (pintype "passive"))
    )
    (net (code "34") (name "LEDS11_3V3") (class "Default")
      (node (ref "SN74HCT245DWR") (pin "7") (pinfunction "A6_7") (pintype "bidirectional"))
      (node (ref "U1") (pin "24") (pinfunction "IO2_24") (pintype "bidirectional"))
    )
    (net (code "35") (name "LEDS11_5V") (class "Default")
      (node (ref "3X8_24_PIN_LED_OUTPUT") (pin "5") (pinfunction "5_5") (pintype "bidirectional"))
      (node (ref "R8") (pin "2") (pinfunction "2_2") (pintype "passive"))
    )
    (net (code "36") (name "LEDS12_3V3") (class "Default")
      (node (ref "SN74HCT245DWR") (pin "6") (pinfunction "A5_6") (pintype "bidirectional"))
      (node (ref "U1") (pin "23") (pinfunction "IO15_23") (pintype "bidirectional"))
    )
    (net (code "37") (name "LEDS12_5V") (class "Default")
      (node (ref "3X8_24_PIN_LED_OUTPUT") (pin "6") (pinfunction "6_6") (pintype "bidirectional"))
      (node (ref "R9") (pin "2") (pinfunction "2_2") (pintype "passive"))
    )
    (net (code "38") (name "LEFT_CHANNEL") (class "Default")
      (node (ref "R21") (pin "2") (pinfunction "2_2") (pintype "passive"))
      (node (ref "U4") (pin "14") (pinfunction "VINR_14") (pintype "input"))
    )
    (net (code "39") (name "LRCK") (class "Default")
      (node (ref "U1") (pin "4") (pinfunction "SENSOR_VP_4") (pintype "input"))
      (node (ref "U4") (pin "7") (pinfunction "LRCK_7") (pintype "bidirectional"))
    )
    (net (code "40") (name "MIC") (class "Default")
      (node (ref "J1") (pin "1") (pinfunction "SLEEVE_1") (pintype "passive"))
    )
    (net (code "41") (name "MISO") (class "Default")
      (node (ref "J6") (pin "MISO") (pinfunction "MISO_MISO") (pintype "bidirectional"))
      (node (ref "U$1") (pin "6") (pinfunction "SO_6") (pintype "output"))
      (node (ref "U$2") (pin "SDDATA0") (pinfunction "SDDATA0_SDDATA0") (pintype "bidirectional"))
      (node (ref "U1") (pin "14") (pinfunction "IO12_14") (pintype "bidirectional"))
    )
    (net (code "42") (name "MOSI") (class "Default")
      (node (ref "J6") (pin "MOSI") (pinfunction "MOSI_MOSI") (pintype "bidirectional"))
      (node (ref "U$1") (pin "7") (pinfunction "SI_7") (pintype "input"))
      (node (ref "U$2") (pin "SDCMD") (pinfunction "SDCMD_SDCMD") (pintype "bidirectional"))
      (node (ref "U1") (pin "16") (pinfunction "IO13_16") (pintype "bidirectional"))
    )
    (net (code "43") (name "Net-(C19-Pad1)") (class "Default")
      (node (ref "C19") (pin "1") (pinfunction "1_1") (pintype "passive"))
      (node (ref "R15") (pin "1") (pinfunction "1_1") (pintype "passive"))
      (node (ref "R22") (pin "2") (pinfunction "2_2") (pintype "passive"))
    )
    (net (code "44") (name "Net-(C22-Pad2)") (class "Default")
      (node (ref "C22") (pin "2") (pinfunction "2_2") (pintype "passive"))
      (node (ref "R20") (pin "1") (pinfunction "1_1") (pintype "passive"))
    )
    (net (code "45") (name "Net-(C23-Pad2)") (class "Default")
      (node (ref "C23") (pin "2") (pinfunction "2_2") (pintype "passive"))
      (node (ref "R21") (pin "1") (pinfunction "1_1") (pintype "passive"))
    )
    (net (code "46") (name "Net-(C26-Pad1)") (class "Default")
      (node (ref "C26") (pin "1") (pinfunction "1_1") (pintype "passive"))
      (node (ref "R23") (pin "2") (pinfunction "2_2") (pintype "passive"))
      (node (ref "R24") (pin "1") (pinfunction "1_1") (pintype "passive"))
    )
    (net (code "47") (name "Net-(J1-RING1)") (class "Default")
      (node (ref "C20") (pin "1") (pinfunction "1_1") (pintype "passive"))
      (node (ref "C22") (pin "1") (pinfunction "1_1") (pintype "passive"))
      (node (ref "J1") (pin "3") (pinfunction "RING1_3") (pintype "passive"))
    )
    (net (code "48") (name "Net-(J1-TIP)") (class "Default")
      (node (ref "C21") (pin "1") (pinfunction "1_1") (pintype "passive"))
      (node (ref "C23") (pin "1") (pinfunction "1_1") (pintype "passive"))
      (node (ref "J1") (pin "2") (pinfunction "TIP_2") (pintype "passive"))
    )
    (net (code "49") (name "Net-(R10-Pad2)") (class "Default")
      (node (ref "R10") (pin "2") (pinfunction "2_2") (pintype "passive"))
      (node (ref "S1") (pin "1") (pinfunction "1_1") (pintype "passive"))
    )
    (net (code "50") (name "Net-(SN74HCT245DWR-B5)") (class "Default")
      (node (ref "R9") (pin "1") (pinfunction "1_1") (pintype "passive"))
      (node (ref "SN74HCT245DWR") (pin "14") (pinfunction "B5_14") (pintype "bidirectional"))
    )
    (net (code "51") (name "Net-(SN74HCT245DWR-B6)") (class "Default")
      (node (ref "R8") (pin "1") (pinfunction "1_1") (pintype "passive"))
      (node (ref "SN74HCT245DWR") (pin "13") (pinfunction "B6_13") (pintype "bidirectional"))
    )
    (net (code "52") (name "Net-(SN74HCT245DWR-B7)") (class "Default")
      (node (ref "R6") (pin "1") (pinfunction "1_1") (pintype "passive"))
      (node (ref "SN74HCT245DWR") (pin "12") (pinfunction "B7_12") (pintype "bidirectional"))
    )
    (net (code "53") (name "Net-(SN74HCT245DWR-B8)") (class "Default")
      (node (ref "R5") (pin "1") (pinfunction "1_1") (pintype "passive"))
      (node (ref "SN74HCT245DWR") (pin "11") (pinfunction "B8_11") (pintype "bidirectional"))
    )
    (net (code "54") (name "Net-(SN74HCT245DWR1-B1)") (class "Default")
      (node (ref "R30") (pin "1") (pinfunction "1_1") (pintype "passive"))
      (node (ref "SN74HCT245DWR1") (pin "18") (pinfunction "B1_18") (pintype "bidirectional"))
    )
    (net (code "55") (name "Net-(SN74HCT245DWR1-B2)") (class "Default")
      (node (ref "R25") (pin "1") (pinfunction "1_1") (pintype "passive"))
      (node (ref "SN74HCT245DWR1") (pin "17") (pinfunction "B2_17") (pintype "bidirectional"))
    )
    (net (code "56") (name "Net-(SN74HCT245DWR1-B3)") (class "Default")
      (node (ref "R29") (pin "1") (pinfunction "1_1") (pintype "passive"))
      (node (ref "SN74HCT245DWR1") (pin "16") (pinfunction "B3_16") (pintype "bidirectional"))
    )
    (net (code "57") (name "Net-(SN74HCT245DWR1-B4)") (class "Default")
      (node (ref "R28") (pin "1") (pinfunction "1_1") (pintype "passive"))
      (node (ref "SN74HCT245DWR1") (pin "15") (pinfunction "B4_15") (pintype "bidirectional"))
    )
    (net (code "58") (name "Net-(SN74HCT245DWR1-B5)") (class "Default")
      (node (ref "R27") (pin "1") (pinfunction "1_1") (pintype "passive"))
      (node (ref "SN74HCT245DWR1") (pin "14") (pinfunction "B5_14") (pintype "bidirectional"))
    )
    (net (code "59") (name "Net-(SN74HCT245DWR1-B6)") (class "Default")
      (node (ref "R26") (pin "1") (pinfunction "1_1") (pintype "passive"))
      (node (ref "SN74HCT245DWR1") (pin "13") (pinfunction "B6_13") (pintype "bidirectional"))
    )
    (net (code "60") (name "Net-(SN74HCT245DWR1-B7)") (class "Default")
      (node (ref "R4") (pin "1") (pinfunction "1_1") (pintype "passive"))
      (node (ref "SN74HCT245DWR1") (pin "12") (pinfunction "B7_12") (pintype "bidirectional"))
    )
    (net (code "61") (name "Net-(SN74HCT245DWR1-B8)") (class "Default")
      (node (ref "R7") (pin "1") (pinfunction "1_1") (pintype "passive"))
      (node (ref "SN74HCT245DWR1") (pin "11") (pinfunction "B8_11") (pintype "bidirectional"))
    )
    (net (code "62") (name "Net-(U$1-LEDA)") (class "Default")
      (node (ref "R18") (pin "1") (pinfunction "1_1") (pintype "passive"))
      (node (ref "U$1") (pin "27") (pinfunction "LEDA_27") (pintype "output"))
    )
    (net (code "63") (name "Net-(U$1-LEDB)") (class "Default")
      (node (ref "R17") (pin "1") (pinfunction "1_1") (pintype "passive"))
      (node (ref "U$1") (pin "26") (pinfunction "LEDB_26") (pintype "output"))
    )
    (net (code "64") (name "Net-(U$1-OSC1)") (class "Default")
      (node (ref "C17") (pin "1") (pinfunction "1_1") (pintype "passive"))
      (node (ref "U$1") (pin "23") (pinfunction "OSC1_23") (pintype "input"))
      (node (ref "U$3") (pin "3") (pinfunction "OUT/IN_3") (pintype "bidirectional"))
    )
    (net (code "65") (name "Net-(U$1-OSC2)") (class "Default")
      (node (ref "C12") (pin "1") (pinfunction "1_1") (pintype "passive"))
      (node (ref "U$1") (pin "24") (pinfunction "OSC2_24") (pintype "output"))
      (node (ref "U$3") (pin "1") (pinfunction "IN/OUT_1") (pintype "bidirectional"))
    )
    (net (code "66") (name "Net-(U$1-RBIAS)") (class "Default")
      (node (ref "R16") (pin "1") (pinfunction "1_1") (pintype "passive"))
      (node (ref "U$1") (pin "14") (pinfunction "RBIAS_14") (pintype "input"))
    )
    (net (code "67") (name "Net-(U$1-VCAP)") (class "Default")
      (node (ref "C11") (pin "1") (pinfunction "1_1") (pintype "passive"))
      (node (ref "C18") (pin "1") (pinfunction "1_1") (pintype "passive"))
      (node (ref "U$1") (pin "1") (pinfunction "VCAP_1") (pintype "input"))
    )
    (net (code "68") (name "Net-(U2-TXD)") (class "Default")
      (node (ref "R14") (pin "1") (pinfunction "1_1") (pintype "passive"))
      (node (ref "U2") (pin "21") (pinfunction "TXD_21") (pintype "output"))
    )
    (net (code "69") (name "Net-(U2-VDD)") (class "Default")
      (node (ref "C1") (pin "1") (pinfunction "1_1") (pintype "passive"))
      (node (ref "C8") (pin "1") (pinfunction "1_1") (pintype "passive"))
      (node (ref "U2") (pin "6") (pinfunction "VDD_6") (pintype "power_in"))
    )
    (net (code "70") (name "Net-(U3-B1)") (class "Default")
      (node (ref "R13") (pin "2") (pinfunction "2_2") (pintype "passive"))
      (node (ref "U3") (pin "5") (pinfunction "B1_5") (pintype "passive"))
    )
    (net (code "71") (name "Net-(U3-B2)") (class "Default")
      (node (ref "R11") (pin "1") (pinfunction "1_1") (pintype "passive"))
      (node (ref "U3") (pin "2") (pinfunction "B2_2") (pintype "passive"))
    )
    (net (code "72") (name "Net-(U4-AGND)") (class "Default")
      (node (ref "C2") (pin "1") (pinfunction "1_1") (pintype "passive"))
      (node (ref "C4") (pin "1") (pinfunction "1_1") (pintype "passive"))
      (node (ref "U4") (pin "2") (pinfunction "AGND_2") (pintype "power_in"))
    )
    (net (code "73") (name "Net-(U4-FMT)") (class "Default")
      (node (ref "R19") (pin "1") (pinfunction "1_1") (pintype "passive"))
      (node (ref "U4") (pin "10") (pinfunction "MD0_10") (pintype "input"))
      (node (ref "U4") (pin "11") (pinfunction "MD1_11") (pintype "input"))
      (node (ref "U4") (pin "12") (pinfunction "FMT_12") (pintype "input"))
    )
    (net (code "74") (name "Net-(U4-VREF)") (class "Default")
      (node (ref "C15") (pin "2") (pinfunction "2_2") (pintype "passive"))
      (node (ref "C16") (pin "2") (pinfunction "2_2") (pintype "passive"))
      (node (ref "U4") (pin "1") (pinfunction "VREF_1") (pintype "power_in"))
    )
    (net (code "75") (name "RIGHT_CHANNEL") (class "Default")
      (node (ref "J3") (pin "1") (pinfunction "1_1") (pintype "passive"))
      (node (ref "R20") (pin "2") (pinfunction "2_2") (pintype "passive"))
      (node (ref "U4") (pin "13") (pinfunction "VINL_13") (pintype "input"))
    )
    (net (code "76") (name "RIGHT_GAIN") (class "Default")
      (node (ref "J3") (pin "2") (pinfunction "2_2") (pintype "passive"))
    )
    (net (code "77") (name "RTS") (class "Default")
      (node (ref "R11") (pin "2") (pinfunction "2_2") (pintype "passive"))
      (node (ref "U2") (pin "19") (pinfunction "RTS_19") (pintype "output"))
      (node (ref "U3") (pin "4") (pinfunction "E1_4") (pintype "passive"))
    )
    (net (code "78") (name "RX0") (class "Default")
      (node (ref "J6") (pin "RX0") (pinfunction "RX_RX0") (pintype "bidirectional"))
      (node (ref "R14") (pin "2") (pinfunction "2_2") (pintype "passive"))
      (node (ref "U1") (pin "34") (pinfunction "RXD0_34") (pintype "bidirectional"))
    )
    (net (code "79") (name "SCK") (class "Default")
      (node (ref "J6") (pin "SCK") (pinfunction "SCK_SCK") (pintype "bidirectional"))
      (node (ref "U$1") (pin "8") (pinfunction "SCK_8") (pintype "input"))
      (node (ref "U$2") (pin "SDCLK") (pinfunction "SDCLK_SDCLK") (pintype "bidirectional"))
      (node (ref "U1") (pin "13") (pinfunction "IO14_13") (pintype "bidirectional"))
    )
    (net (code "80") (name "SCKI") (class "Default")
      (node (ref "U1") (pin "37") (pinfunction "IO23_37") (pintype "bidirectional"))
      (node (ref "U4") (pin "6") (pinfunction "SCKI_6") (pintype "input"))
    )
    (net (code "81") (name "SD_CMD") (class "Default")
      (node (ref "J5") (pin "3") (pinfunction "3_3") (pintype "passive"))
      (node (ref "U$2") (pin "CMD") (pinfunction "CMD_CMD") (pintype "bidirectional"))
    )
    (net (code "82") (name "SD_CS") (class "Default")
      (node (ref "U$2") (pin "SDDATA3") (pinfunction "SDDATA3_SDDATA3") (pintype "bidirectional"))
      (node (ref "U1") (pin "7") (pinfunction "IO35_7") (pintype "input"))
    )
    (net (code "83") (name "SD_D0") (class "Default")
      (node (ref "J5") (pin "7") (pinfunction "7_7") (pintype "passive"))
      (node (ref "U$2") (pin "DATA0") (pinfunction "DATA0_DATA0") (pintype "bidirectional"))
    )
    (net (code "84") (name "SD_D1") (class "Default")
      (node (ref "J5") (pin "8") (pinfunction "8_8") (pintype "passive"))
      (node (ref "U$2") (pin "DATA1") (pinfunction "DATA1_DATA1") (pintype "bidirectional"))
    )
    (net (code "85") (name "SD_D2") (class "Default")
      (node (ref "J5") (pin "1") (pinfunction "1_1") (pintype "passive"))
      (node (ref "U$2") (pin "DATA2") (pinfunction "DATA2_DATA2") (pintype "bidirectional"))
    )
    (net (code "86") (name "SD_D3") (class "Default")
      (node (ref "J5") (pin "2") (pinfunction "2_2") (pintype "passive"))
      (node (ref "U$2") (pin "DATA3") (pinfunction "DATA3_DATA3") (pintype "bidirectional"))
    )
    (net (code "87") (name "SD_SCK") (class "Default")
      (node (ref "J5") (pin "5") (pinfunction "5_5") (pintype "passive"))
      (node (ref "U$2") (pin "CLK") (pinfunction "CLK_CLK") (pintype "bidirectional"))
    )
    (net (code "88") (name "TPIN+") (class "Default")
      (node (ref "P1") (pin "R7") (pinfunction "RD+_R7") (pintype "input"))
      (node (ref "R24") (pin "2") (pinfunction "2_2") (pintype "passive"))
      (node (ref "U$1") (pin "13") (pinfunction "TPIN+_13") (pintype "input"))
    )
    (net (code "89") (name "TPIN-") (class "Default")
      (node (ref "P1") (pin "R8") (pinfunction "RD-_R8") (pintype "input"))
      (node (ref "R23") (pin "1") (pinfunction "1_1") (pintype "passive"))
      (node (ref "U$1") (pin "12") (pinfunction "TPIN-_12") (pintype "input"))
    )
    (net (code "90") (name "TPOUT+") (class "Default")
      (node (ref "P1") (pin "R1") (pinfunction "TD+_R1") (pintype "input"))
      (node (ref "R15") (pin "2") (pinfunction "2_2") (pintype "passive"))
      (node (ref "U$1") (pin "17") (pinfunction "TPOUT+_17") (pintype "output"))
    )
    (net (code "91") (name "TPOUT-") (class "Default")
      (node (ref "P1") (pin "R2") (pinfunction "TD-_R2") (pintype "input"))
      (node (ref "R22") (pin "1") (pinfunction "1_1") (pintype "passive"))
      (node (ref "U$1") (pin "16") (pinfunction "TPOUT-_16") (pintype "output"))
    )
    (net (code "92") (name "TX_CONTROLLER") (class "Default")
      (node (ref "J6") (pin "TX0") (pinfunction "TX_TX0") (pintype "bidirectional"))
      (node (ref "R1") (pin "2") (pinfunction "2_2") (pintype "passive"))
      (node (ref "U2") (pin "20") (pinfunction "RXD_20") (pintype "input"))
    )
    (net (code "93") (name "VDD3V3") (class "Default")
      (node (ref "5V_TO_3V3_REGULATOR") (pin "2") (pinfunction "OUT_2") (pintype "passive"))
      (node (ref "5V_TO_3V3_REGULATOR") (pin "4") (pinfunction "OUT_4") (pintype "passive"))
      (node (ref "C10") (pin "1") (pinfunction "1_1") (pintype "passive"))
      (node (ref "C13") (pin "1") (pinfunction "1_1") (pintype "passive"))
      (node (ref "C14") (pin "1") (pinfunction "1_1") (pintype "passive"))
      (node (ref "C6") (pin "1") (pinfunction "1_1") (pintype "passive"))
      (node (ref "C7") (pin "1") (pinfunction "1_1") (pintype "passive"))
      (node (ref "J3") (pin "3") (pinfunction "3_3") (pintype "passive"))
      (node (ref "J5") (pin "4") (pinfunction "4_4") (pintype "passive"))
      (node (ref "J6") (pin "VCC") (pinfunction "VCC_VCC") (pintype "bidirectional"))
      (node (ref "L1") (pin "1") (pinfunction "1_1") (pintype "passive"))
      (node (ref "R12") (pin "2") (pinfunction "2_2") (pintype "passive"))
      (node (ref "U$1") (pin "15") (pinfunction "VDDTX_15") (pintype "power_in"))
      (node (ref "U$1") (pin "19") (pinfunction "VDDRX_19") (pintype "power_in"))
      (node (ref "U$1") (pin "20") (pinfunction "VDDPLL_20") (pintype "power_in"))
      (node (ref "U$1") (pin "25") (pinfunction "VDDOSC_25") (pintype "power_in"))
      (node (ref "U$1") (pin "28") (pinfunction "VDD_28") (pintype "power_in"))
      (node (ref "U$2") (pin "VCC") (pinfunction "VCC_VCC") (pintype "bidirectional"))
      (node (ref "U1") (pin "2") (pinfunction "VDD3V3_2") (pintype "power_in"))
      (node (ref "U4") (pin "4") (pinfunction "VDD_4") (pintype "power_in"))
    )
    (net (code "94") (name "VDD5V") (class "Default")
      (node (ref "3X8_24_PIN_LED_OUTPUT") (pin "17") (pinfunction "17_17") (pintype "bidirectional"))
      (node (ref "3X8_24_PIN_LED_OUTPUT") (pin "18") (pinfunction "18_18") (pintype "bidirectional"))
      (node (ref "5V_TO_3V3_REGULATOR") (pin "3") (pinfunction "IN_3") (pintype "input"))
      (node (ref "C2") (pin "2") (pinfunction "2_2") (pintype "passive"))
      (node (ref "C24") (pin "1") (pinfunction "1_1") (pintype "passive"))
      (node (ref "C25") (pin "1") (pinfunction "1_1") (pintype "passive"))
      (node (ref "C3") (pin "1") (pinfunction "1_1") (pintype "passive"))
      (node (ref "C4") (pin "2") (pinfunction "2_2") (pintype "passive"))
      (node (ref "C5") (pin "1") (pinfunction "1_1") (pintype "passive"))
      (node (ref "C9") (pin "1") (pinfunction "1_1") (pintype "passive"))
      (node (ref "D2") (pin "C") (pinfunction "C_C") (pintype "passive"))
      (node (ref "SN74HCT245DWR") (pin "1") (pinfunction "DIR_1") (pintype "input"))
      (node (ref "SN74HCT245DWR") (pin "20") (pinfunction "VCC_20") (pintype "power_in"))
      (node (ref "SN74HCT245DWR1") (pin "1") (pinfunction "DIR_1") (pintype "input"))
      (node (ref "SN74HCT245DWR1") (pin "20") (pinfunction "VCC_20") (pintype "power_in"))
      (node (ref "U4") (pin "3") (pinfunction "VCC_3") (pintype "power_in"))
    )
    (net (code "95") (name "VDD5VUSB") (class "Default")
      (node (ref "D1") (pin "2") (pinfunction "2_2") (pintype "passive"))
      (node (ref "D2") (pin "A") (pinfunction "A_A") (pintype "passive"))
      (node (ref "J2") (pin "A4") (pinfunction "VBUS1_A4") (pintype "passive"))
      (node (ref "J2") (pin "A9") (pinfunction "VBUS2_A9") (pintype "passive"))
      (node (ref "J2") (pin "B4") (pinfunction "VBUS3_B4") (pintype "passive"))
      (node (ref "J2") (pin "B9") (pinfunction "VBUS4_B9") (pintype "passive"))
      (node (ref "U2") (pin "8") (pinfunction "VBUS_8") (pintype "power_in"))
    )
    (net (code "96") (name "VREGIN") (class "Default")
      (node (ref "U2") (pin "7") (pinfunction "VREGIN_7") (pintype "power_in"))
    )
    (net (code "97") (name "unconnected-(J1-RING1_SWITCH-Pad11)") (class "Default")
      (node (ref "J1") (pin "11") (pinfunction "RING1_SWITCH_11") (pintype "passive"))
    )
    (net (code "98") (name "unconnected-(J1-TIP_SWITCH-Pad10)") (class "Default")
      (node (ref "J1") (pin "10") (pinfunction "TIP_SWITCH_10") (pintype "passive"))
    )
    (net (code "99") (name "unconnected-(J2-CC1-PadA5)") (class "Default")
      (node (ref "J2") (pin "A5") (pinfunction "CC1_A5") (pintype "passive"))
    )
    (net (code "100") (name "unconnected-(J2-CC2-PadB5)") (class "Default")
      (node (ref "J2") (pin "B5") (pinfunction "CC2_B5") (pintype "passive"))
    )
    (net (code "101") (name "unconnected-(J2-RX1+-PadB11)") (class "Default")
      (node (ref "J2") (pin "B11") (pinfunction "RX1+_B11") (pintype "passive"))
    )
    (net (code "102") (name "unconnected-(J2-RX1--PadB10)") (class "Default")
      (node (ref "J2") (pin "B10") (pinfunction "RX1-_B10") (pintype "passive"))
    )
    (net (code "103") (name "unconnected-(J2-RX2+-PadA11)") (class "Default")
      (node (ref "J2") (pin "A11") (pinfunction "RX2+_A11") (pintype "passive"))
    )
    (net (code "104") (name "unconnected-(J2-RX2--PadA10)") (class "Default")
      (node (ref "J2") (pin "A10") (pinfunction "RX2-_A10") (pintype "passive"))
    )
    (net (code "105") (name "unconnected-(J2-SBU1-PadA8)") (class "Default")
      (node (ref "J2") (pin "A8") (pinfunction "SBU1_A8") (pintype "passive"))
    )
    (net (code "106") (name "unconnected-(J2-SBU2-PadB8)") (class "Default")
      (node (ref "J2") (pin "B8") (pinfunction "SBU2_B8") (pintype "passive"))
    )
    (net (code "107") (name "unconnected-(J2-TX1+-PadA2)") (class "Default")
      (node (ref "J2") (pin "A2") (pinfunction "TX1+_A2") (pintype "passive"))
    )
    (net (code "108") (name "unconnected-(J2-TX1--PadA3)") (class "Default")
      (node (ref "J2") (pin "A3") (pinfunction "TX1-_A3") (pintype "passive"))
    )
    (net (code "109") (name "unconnected-(J2-TX2+-PadB2)") (class "Default")
      (node (ref "J2") (pin "B2") (pinfunction "TX2+_B2") (pintype "passive"))
    )
    (net (code "110") (name "unconnected-(J2-TX2--PadB3)") (class "Default")
      (node (ref "J2") (pin "B3") (pinfunction "TX2-_B3") (pintype "passive"))
    )
    (net (code "111") (name "unconnected-(P1-PadR4)") (class "Default")
      (node (ref "P1") (pin "R4") (pinfunction "R4_R4") (pintype "input"))
    )
    (net (code "112") (name "unconnected-(P1-PadR5)") (class "Default")
      (node (ref "P1") (pin "R5") (pinfunction "R5_R5") (pintype "input"))
    )
    (net (code "113") (name "unconnected-(P1-PadR6)") (class "Default")
      (node (ref "P1") (pin "R6") (pinfunction "R6_R6") (pintype "input"))
    )
    (net (code "114") (name "unconnected-(SN74HCT245DWR-A1-Pad2)") (class "Default")
      (node (ref "SN74HCT245DWR") (pin "2") (pinfunction "A1_2") (pintype "bidirectional"))
    )
    (net (code "115") (name "unconnected-(SN74HCT245DWR-A2-Pad3)") (class "Default")
      (node (ref "SN74HCT245DWR") (pin "3") (pinfunction "A2_3") (pintype "bidirectional"))
    )
    (net (code "116") (name "unconnected-(SN74HCT245DWR-A3-Pad4)") (class "Default")
      (node (ref "SN74HCT245DWR") (pin "4") (pinfunction "A3_4") (pintype "bidirectional"))
    )
    (net (code "117") (name "unconnected-(SN74HCT245DWR-A4-Pad5)") (class "Default")
      (node (ref "SN74HCT245DWR") (pin "5") (pinfunction "A4_5") (pintype "bidirectional"))
    )
    (net (code "118") (name "unconnected-(SN74HCT245DWR-B1-Pad18)") (class "Default")
      (node (ref "SN74HCT245DWR") (pin "18") (pinfunction "B1_18") (pintype "bidirectional"))
    )
    (net (code "119") (name "unconnected-(SN74HCT245DWR-B2-Pad17)") (class "Default")
      (node (ref "SN74HCT245DWR") (pin "17") (pinfunction "B2_17") (pintype "bidirectional"))
    )
    (net (code "120") (name "unconnected-(SN74HCT245DWR-B3-Pad16)") (class "Default")
      (node (ref "SN74HCT245DWR") (pin "16") (pinfunction "B3_16") (pintype "bidirectional"))
    )
    (net (code "121") (name "unconnected-(SN74HCT245DWR-B4-Pad15)") (class "Default")
      (node (ref "SN74HCT245DWR") (pin "15") (pinfunction "B4_15") (pintype "bidirectional"))
    )
    (net (code "122") (name "unconnected-(U$1-CLKOUT-Pad3)") (class "Default")
      (node (ref "U$1") (pin "3") (pinfunction "CLKOUT_3") (pintype "output"))
    )
    (net (code "123") (name "unconnected-(U$1-NC-Pad5)") (class "Default")
      (node (ref "U$1") (pin "5") (pinfunction "NC_5") (pintype "no_connect"))
    )
    (net (code "124") (name "unconnected-(U$2-PadESD1)") (class "Default")
      (node (ref "U$2") (pin "ESD1") (pinfunction "ESD1_ESD1") (pintype "bidirectional"))
    )
    (net (code "125") (name "unconnected-(U$2-PadESD2)") (class "Default")
      (node (ref "U$2") (pin "ESD2") (pinfunction "ESD2_ESD2") (pintype "bidirectional"))
    )
    (net (code "126") (name "unconnected-(U$2-PadESD3)") (class "Default")
      (node (ref "U$2") (pin "ESD3") (pinfunction "ESD3_ESD3") (pintype "bidirectional"))
    )
    (net (code "127") (name "unconnected-(U$2-PadGND)") (class "Default")
      (node (ref "U$2") (pin "GND") (pinfunction "GND_GND") (pintype "bidirectional"))
    )
    (net (code "128") (name "unconnected-(U$2-PadSDDATA1)") (class "Default")
      (node (ref "U$2") (pin "SDDATA1") (pinfunction "SDDATA1_SDDATA1") (pintype "bidirectional"))
    )
    (net (code "129") (name "unconnected-(U$2-PadSDDATA2)") (class "Default")
      (node (ref "U$2") (pin "SDDATA2") (pinfunction "SDDATA2_SDDATA2") (pintype "bidirectional"))
    )
    (net (code "130") (name "unconnected-(U1-SCK{slash}CLK-Pad20)") (class "Default")
      (node (ref "U1") (pin "20") (pinfunction "SCK/CLK_20") (pintype "bidirectional"))
    )
    (net (code "131") (name "unconnected-(U1-SCS{slash}CMD-Pad19)") (class "Default")
      (node (ref "U1") (pin "19") (pinfunction "SCS/CMD_19") (pintype "bidirectional"))
    )
    (net (code "132") (name "unconnected-(U1-SDI{slash}SD1-Pad22)") (class "Default")
      (node (ref "U1") (pin "22") (pinfunction "SDI/SD1_22") (pintype "bidirectional"))
    )
    (net (code "133") (name "unconnected-(U1-SDO{slash}SD0-Pad21)") (class "Default")
      (node (ref "U1") (pin "21") (pinfunction "SDO/SD0_21") (pintype "bidirectional"))
    )
    (net (code "134") (name "unconnected-(U1-SHD{slash}SD2-Pad17)") (class "Default")
      (node (ref "U1") (pin "17") (pinfunction "SHD/SD2_17") (pintype "bidirectional"))
    )
    (net (code "135") (name "unconnected-(U1-SWP{slash}SD3-Pad18)") (class "Default")
      (node (ref "U1") (pin "18") (pinfunction "SWP/SD3_18") (pintype "bidirectional"))
    )
    (net (code "136") (name "unconnected-(U2-CTS-Pad18)") (class "Default")
      (node (ref "U2") (pin "18") (pinfunction "CTS_18") (pintype "input"))
    )
    (net (code "137") (name "unconnected-(U2-DCD-Pad24)") (class "Default")
      (node (ref "U2") (pin "24") (pinfunction "DCD_24") (pintype "bidirectional"))
    )
    (net (code "138") (name "unconnected-(U2-DSR-Pad22)") (class "Default")
      (node (ref "U2") (pin "22") (pinfunction "DSR_22") (pintype "bidirectional"))
    )
    (net (code "139") (name "unconnected-(U2-GPIO.0{slash}TXT-Pad14)") (class "Default")
      (node (ref "U2") (pin "14") (pinfunction "GPIO.0/TXT_14") (pintype "bidirectional"))
    )
    (net (code "140") (name "unconnected-(U2-GPIO.1{slash}RXT-Pad13)") (class "Default")
      (node (ref "U2") (pin "13") (pinfunction "GPIO.1/RXT_13") (pintype "bidirectional"))
    )
    (net (code "141") (name "unconnected-(U2-GPIO.2{slash}RS485-Pad12)") (class "Default")
      (node (ref "U2") (pin "12") (pinfunction "GPIO.2/RS485_12") (pintype "bidirectional"))
    )
    (net (code "142") (name "unconnected-(U2-GPIO.3{slash}WAKEUP-Pad11)") (class "Default")
      (node (ref "U2") (pin "11") (pinfunction "GPIO.3/WAKEUP_11") (pintype "bidirectional"))
    )
    (net (code "143") (name "unconnected-(U2-RI{slash}CLK-Pad1)") (class "Default")
      (node (ref "U2") (pin "1") (pinfunction "RI/CLK_1") (pintype "input"))
    )
    (net (code "144") (name "unconnected-(U2-SUSPEND-Pad17)") (class "Default")
      (node (ref "U2") (pin "17") (pinfunction "SUSPEND_17") (pintype "output"))
    )
    (net (code "145") (name "unconnected-(U2-VIO-Pad5)") (class "Default")
      (node (ref "U2") (pin "5") (pinfunction "VIO_5") (pintype "bidirectional"))
    )
    (net (code "146") (name "unconnected-(U2-~{RST}-Pad9)") (class "Default")
      (node (ref "U2") (pin "9") (pinfunction "~{RST}_9") (pintype "input"))
    )
    (net (code "147") (name "unconnected-(U2-~{SUSPEND}-Pad15)") (class "Default")
      (node (ref "U2") (pin "15") (pinfunction "~{SUSPEND}_15") (pintype "output"))
    )
  )
)
